# 07_DDR3.net
KiCad netlist of a schematic drawn in Altium Designer
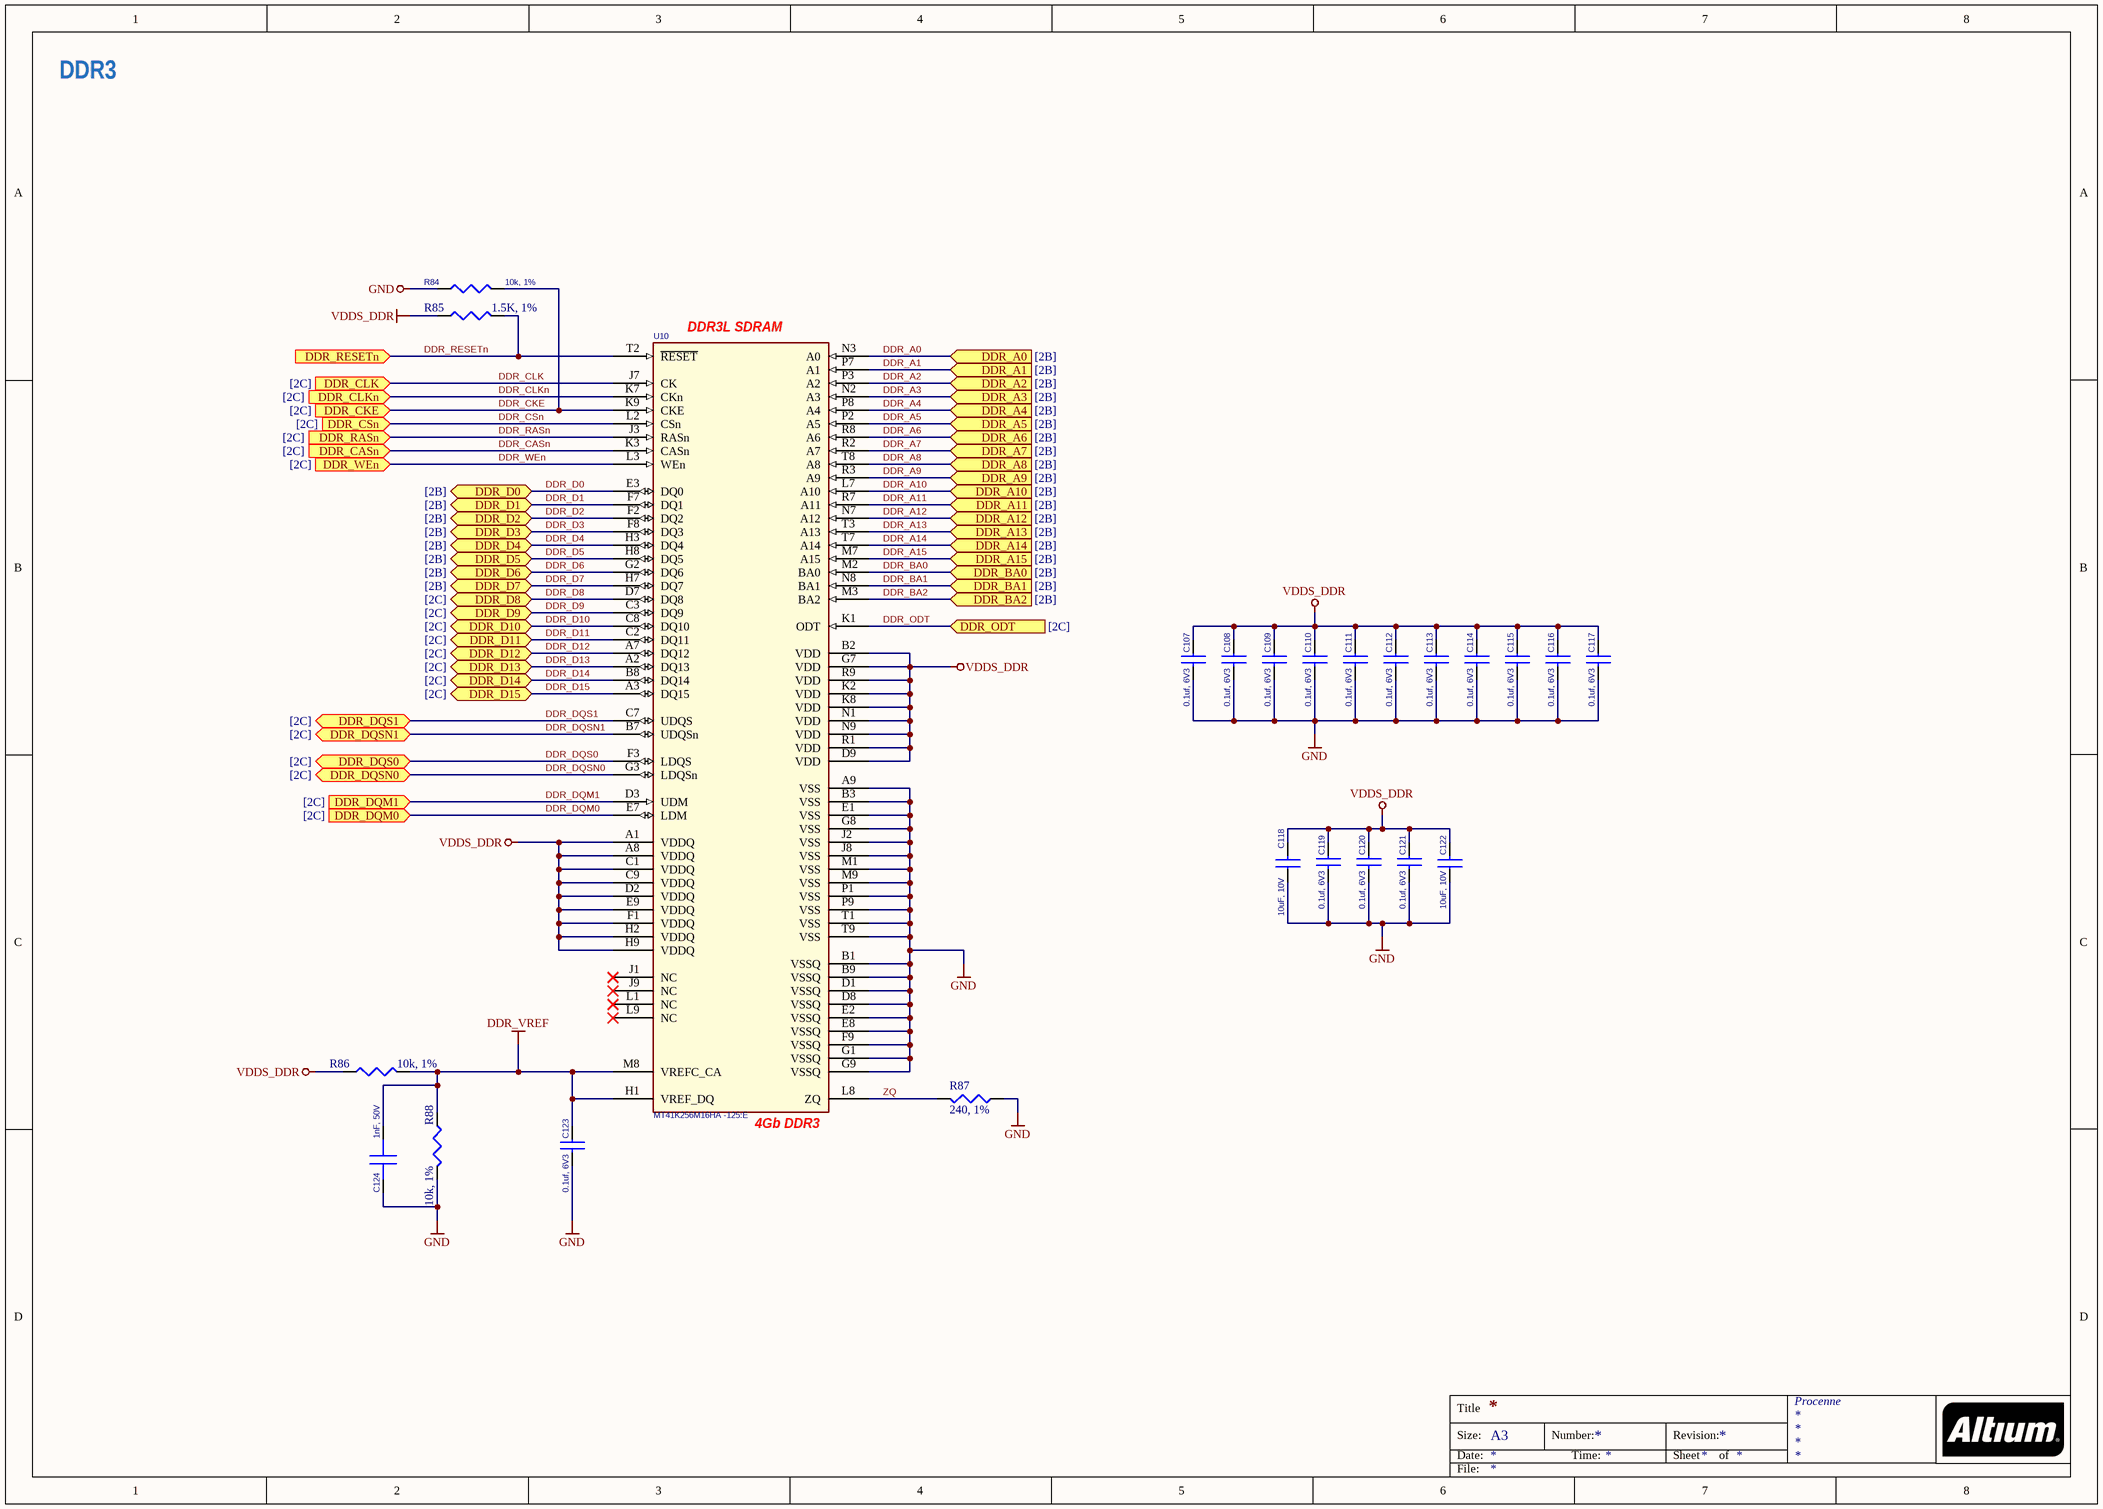
[diagram p0: 07_DDR3.SchDoc]

(export (version "E")
  (design (tool "Eeschema 10.0.6"))
  (components
    (comp (ref "C107")
      (value "0.1uf, 6V3")
      (footprint "402")
      (description "CAP CER 0.1UF 6.3V 10% X5R 0402")
      (fields
        (field (name "MANUFACTURER") "TDK Corporation")
        (field (name "MANUFACTURER PART NUMBER") "C1005X5R0J104K050BA")
      )
      (libsource (lib "BEAGLEBONEBLACK_REV A5B") (part "CAP_0.01uf_X7R_16V_10%_0402"))
    )
    (comp (ref "C108")
      (value "0.1uf, 6V3")
      (footprint "402")
      (description "CAP CER 0.1UF 6.3V 10% X5R 0402")
      (fields
        (field (name "MANUFACTURER") "TDK Corporation")
        (field (name "MANUFACTURER PART NUMBER") "C1005X5R0J104K050BA")
      )
      (libsource (lib "BEAGLEBONEBLACK_REV A5B") (part "CAP_0.01uf_X7R_16V_10%_0402"))
    )
    (comp (ref "C109")
      (value "0.1uf, 6V3")
      (footprint "402")
      (description "CAP CER 0.1UF 6.3V 10% X5R 0402")
      (fields
        (field (name "MANUFACTURER") "TDK Corporation")
        (field (name "MANUFACTURER PART NUMBER") "C1005X5R0J104K050BA")
      )
      (libsource (lib "BEAGLEBONEBLACK_REV A5B") (part "CAP_0.01uf_X7R_16V_10%_0402"))
    )
    (comp (ref "C110")
      (value "0.1uf, 6V3")
      (footprint "402")
      (description "CAP CER 0.1UF 6.3V 10% X5R 0402")
      (fields
        (field (name "MANUFACTURER") "TDK Corporation")
        (field (name "MANUFACTURER PART NUMBER") "C1005X5R0J104K050BA")
      )
      (libsource (lib "BEAGLEBONEBLACK_REV A5B") (part "CAP_0.01uf_X7R_16V_10%_0402"))
    )
    (comp (ref "C111")
      (value "0.1uf, 6V3")
      (footprint "402")
      (description "CAP CER 0.1UF 6.3V 10% X5R 0402")
      (fields
        (field (name "MANUFACTURER") "TDK Corporation")
        (field (name "MANUFACTURER PART NUMBER") "C1005X5R0J104K050BA")
      )
      (libsource (lib "BEAGLEBONEBLACK_REV A5B") (part "CAP_0.01uf_X7R_16V_10%_0402"))
    )
    (comp (ref "C112")
      (value "0.1uf, 6V3")
      (footprint "402")
      (description "CAP CER 0.1UF 6.3V 10% X5R 0402")
      (fields
        (field (name "MANUFACTURER") "TDK Corporation")
        (field (name "MANUFACTURER PART NUMBER") "C1005X5R0J104K050BA")
      )
      (libsource (lib "BEAGLEBONEBLACK_REV A5B") (part "CAP_0.01uf_X7R_16V_10%_0402"))
    )
    (comp (ref "C113")
      (value "0.1uf, 6V3")
      (footprint "402")
      (description "CAP CER 0.1UF 6.3V 10% X5R 0402")
      (fields
        (field (name "MANUFACTURER") "TDK Corporation")
        (field (name "MANUFACTURER PART NUMBER") "C1005X5R0J104K050BA")
      )
      (libsource (lib "BEAGLEBONEBLACK_REV A5B") (part "CAP_0.01uf_X7R_16V_10%_0402"))
    )
    (comp (ref "C114")
      (value "0.1uf, 6V3")
      (footprint "402")
      (description "CAP CER 0.1UF 6.3V 10% X5R 0402")
      (fields
        (field (name "MANUFACTURER") "TDK Corporation")
        (field (name "MANUFACTURER PART NUMBER") "C1005X5R0J104K050BA")
      )
      (libsource (lib "BEAGLEBONEBLACK_REV A5B") (part "CAP_0.01uf_X7R_16V_10%_0402"))
    )
    (comp (ref "C115")
      (value "0.1uf, 6V3")
      (footprint "402")
      (description "CAP CER 0.1UF 6.3V 10% X5R 0402")
      (fields
        (field (name "MANUFACTURER") "TDK Corporation")
        (field (name "MANUFACTURER PART NUMBER") "C1005X5R0J104K050BA")
      )
      (libsource (lib "BEAGLEBONEBLACK_REV A5B") (part "CAP_0.01uf_X7R_16V_10%_0402"))
    )
    (comp (ref "C116")
      (value "0.1uf, 6V3")
      (footprint "402")
      (description "CAP CER 0.1UF 6.3V 10% X5R 0402")
      (fields
        (field (name "MANUFACTURER") "TDK Corporation")
        (field (name "MANUFACTURER PART NUMBER") "C1005X5R0J104K050BA")
      )
      (libsource (lib "BEAGLEBONEBLACK_REV A5B") (part "CAP_0.01uf_X7R_16V_10%_0402"))
    )
    (comp (ref "C117")
      (value "0.1uf, 6V3")
      (footprint "402")
      (description "CAP CER 0.1UF 6.3V 10% X5R 0402")
      (fields
        (field (name "MANUFACTURER") "TDK Corporation")
        (field (name "MANUFACTURER PART NUMBER") "C1005X5R0J104K050BA")
      )
      (libsource (lib "BEAGLEBONEBLACK_REV A5B") (part "CAP_0.01uf_X7R_16V_10%_0402"))
    )
    (comp (ref "C118")
      (value "10uF, 10V")
      (footprint "805")
      (description "CAP CER 10UF 10V Y5V 0805")
      (fields
        (field (name "MANUFACTURER") "TDK Corporation")
        (field (name "MANUFACTURER PART NUMBER") "C2012Y5V1A106Z")
      )
      (libsource (lib "BEAGLEBONEBLACK_REV A5B") (part "CAP_4.7uF_X5R_6.3V_10%_0603"))
    )
    (comp (ref "C119")
      (value "0.1uf, 6V3")
      (footprint "402")
      (description "CAP CER 0.1UF 6.3V 10% X5R 0402")
      (fields
        (field (name "MANUFACTURER") "TDK Corporation")
        (field (name "MANUFACTURER PART NUMBER") "C1005X5R0J104K050BA")
      )
      (libsource (lib "BEAGLEBONEBLACK_REV A5B") (part "CAP_0.01uf_X7R_16V_10%_0402"))
    )
    (comp (ref "C120")
      (value "0.1uf, 6V3")
      (footprint "402")
      (description "CAP CER 0.1UF 6.3V 10% X5R 0402")
      (fields
        (field (name "MANUFACTURER") "TDK Corporation")
        (field (name "MANUFACTURER PART NUMBER") "C1005X5R0J104K050BA")
      )
      (libsource (lib "BEAGLEBONEBLACK_REV A5B") (part "CAP_0.01uf_X7R_16V_10%_0402"))
    )
    (comp (ref "C121")
      (value "0.1uf, 6V3")
      (footprint "402")
      (description "CAP CER 0.1UF 6.3V 10% X5R 0402")
      (fields
        (field (name "MANUFACTURER") "TDK Corporation")
        (field (name "MANUFACTURER PART NUMBER") "C1005X5R0J104K050BA")
      )
      (libsource (lib "BEAGLEBONEBLACK_REV A5B") (part "CAP_0.01uf_X7R_16V_10%_0402"))
    )
    (comp (ref "C122")
      (value "10uF, 10V")
      (footprint "805")
      (description "CAP CER 10UF 10V Y5V 0805")
      (fields
        (field (name "MANUFACTURER") "TDK Corporation")
        (field (name "MANUFACTURER PART NUMBER") "C2012Y5V1A106Z")
      )
      (libsource (lib "BEAGLEBONEBLACK_REV A5B") (part "CAP_4.7uF_X5R_6.3V_10%_0603"))
    )
    (comp (ref "C123")
      (value "0.1uf, 6V3")
      (footprint "402")
      (description "CAP CER 0.1UF 6.3V 10% X5R 0402")
      (fields
        (field (name "MANUFACTURER") "TDK Corporation")
        (field (name "MANUFACTURER PART NUMBER") "C1005X5R0J104K050BA")
      )
      (libsource (lib "BEAGLEBONEBLACK_REV A5B") (part "CAP_0.01uf_X7R_16V_10%_0402"))
    )
    (comp (ref "C124")
      (value "1nF, 50V")
      (footprint "402")
      (description "CAP CER 1000PF 16V 10% X7R 0402")
      (fields
        (field (name "MANUFACTURER") "Yageo")
        (field (name "MANUFACTURER PART NUMBER") "CC0402KRX7R7BB102")
      )
      (libsource (lib "BEAGLEBONEBLACK_REV A5B") (part "CAP SMD"))
    )
    (comp (ref "R84")
      (value "10k, 1%")
      (footprint "402")
      (description "RES 10K OHM 1/16W 5% 0402 SMD")
      (fields
        (field (name "MANUFACTURER") "Rohm Semiconductor")
        (field (name "MANUFACTURER PART NUMBER") "MCR01MZPJ103")
      )
      (libsource (lib "BEAGLEBONEBLACK_REV A5B") (part "RES_10K_1/16W_1%_0402"))
    )
    (comp (ref "R85")
      (value "1.5K, 1%")
      (footprint "402")
      (description "RES 1.50K OHM 1/16W 1% 0402 SMD")
      (fields
        (field (name "MANUFACTURER") "Yageo")
        (field (name "MANUFACTURER PART NUMBER") "RC0402FR-071K5L")
      )
      (libsource (lib "BEAGLEBONEBLACK_REV A5B") (part "RES_10K_1/16W_1%_0402"))
    )
    (comp (ref "R86")
      (value "10k, 1%")
      (footprint "402")
      (description "RES 10K OHM 1/16W 5% 0402 SMD")
      (fields
        (field (name "MANUFACTURER") "Rohm Semiconductor")
        (field (name "MANUFACTURER PART NUMBER") "MCR01MZPJ103")
      )
      (libsource (lib "BEAGLEBONEBLACK_REV A5B") (part "RES_10K_1/16W_1%_0402"))
    )
    (comp (ref "R87")
      (value "240, 1%")
      (footprint "402")
      (description "RES 240 OHM 1/10W 5% 0402 SMD")
      (fields
        (field (name "MANUFACTURER") "Yageo")
        (field (name "MANUFACTURER PART NUMBER") "RC0402FR-07240RL")
      )
      (libsource (lib "BEAGLEBONEBLACK_REV A5B") (part "RES_10K_1/16W_1%_0402"))
    )
    (comp (ref "R88")
      (value "10k, 1%")
      (footprint "402")
      (description "RES 10K OHM 1/16W 5% 0402 SMD")
      (fields
        (field (name "MANUFACTURER") "Rohm Semiconductor")
        (field (name "MANUFACTURER PART NUMBER") "MCR01MZPJ103")
      )
      (libsource (lib "BEAGLEBONEBLACK_REV A5B") (part "RES_10K_1/16W_1%_0402"))
    )
    (comp (ref "U10")
      (value "MT41K256M16HA -125:E")
      (footprint "BGA96_T9_P8_9X14")
      (description "DDR2 SDRAM 2Gb (256Mx8)")
      (fields
        (field (name "MANUFACTURER") "Micron Technology")
        (field (name "MANUFACTURER PART NUMBER") "MT41K256M16HA-125:E")
      )
      (libsource (lib "BEAGLEBONEBLACK_REV A5B") (part "MT41K256M16HA"))
    )
  )
  (nets
    (net (code "1") (name "/DDR_A0") (class "Default")
      (node (ref "U10") (pin "N3") (pinfunction "A0_N3") (pintype "input"))
    )
    (net (code "2") (name "/DDR_A1") (class "Default")
      (node (ref "U10") (pin "P7") (pinfunction "A1_P7") (pintype "input"))
    )
    (net (code "3") (name "/DDR_A2") (class "Default")
      (node (ref "U10") (pin "P3") (pinfunction "A2_P3") (pintype "input"))
    )
    (net (code "4") (name "/DDR_A3") (class "Default")
      (node (ref "U10") (pin "N2") (pinfunction "A3_N2") (pintype "input"))
    )
    (net (code "5") (name "/DDR_A4") (class "Default")
      (node (ref "U10") (pin "P8") (pinfunction "A4_P8") (pintype "input"))
    )
    (net (code "6") (name "/DDR_A5") (class "Default")
      (node (ref "U10") (pin "P2") (pinfunction "A5_P2") (pintype "input"))
    )
    (net (code "7") (name "/DDR_A6") (class "Default")
      (node (ref "U10") (pin "R8") (pinfunction "A6_R8") (pintype "input"))
    )
    (net (code "8") (name "/DDR_A7") (class "Default")
      (node (ref "U10") (pin "R2") (pinfunction "A7_R2") (pintype "input"))
    )
    (net (code "9") (name "/DDR_A8") (class "Default")
      (node (ref "U10") (pin "T8") (pinfunction "A8_T8") (pintype "input"))
    )
    (net (code "10") (name "/DDR_A9") (class "Default")
      (node (ref "U10") (pin "R3") (pinfunction "A9_R3") (pintype "input"))
    )
    (net (code "11") (name "/DDR_A10") (class "Default")
      (node (ref "U10") (pin "L7") (pinfunction "A10_L7") (pintype "input"))
    )
    (net (code "12") (name "/DDR_A11") (class "Default")
      (node (ref "U10") (pin "R7") (pinfunction "A11_R7") (pintype "input"))
    )
    (net (code "13") (name "/DDR_A12") (class "Default")
      (node (ref "U10") (pin "N7") (pinfunction "A12_N7") (pintype "input"))
    )
    (net (code "14") (name "/DDR_A13") (class "Default")
      (node (ref "U10") (pin "T3") (pinfunction "A13_T3") (pintype "input"))
    )
    (net (code "15") (name "/DDR_A14") (class "Default")
      (node (ref "U10") (pin "T7") (pinfunction "A14_T7") (pintype "input"))
    )
    (net (code "16") (name "/DDR_A15") (class "Default")
      (node (ref "U10") (pin "M7") (pinfunction "A15_M7") (pintype "input"))
    )
    (net (code "17") (name "/DDR_BA0") (class "Default")
      (node (ref "U10") (pin "M2") (pinfunction "BA0_M2") (pintype "input"))
    )
    (net (code "18") (name "/DDR_BA1") (class "Default")
      (node (ref "U10") (pin "N8") (pinfunction "BA1_N8") (pintype "input"))
    )
    (net (code "19") (name "/DDR_BA2") (class "Default")
      (node (ref "U10") (pin "M3") (pinfunction "BA2_M3") (pintype "input"))
    )
    (net (code "20") (name "/DDR_CASn") (class "Default")
      (node (ref "U10") (pin "K3") (pinfunction "CASn_K3") (pintype "input"))
    )
    (net (code "21") (name "/DDR_CKE") (class "Default")
      (node (ref "R84") (pin "2") (pinfunction "2_2") (pintype "passive"))
      (node (ref "U10") (pin "K9") (pinfunction "CKE_K9") (pintype "input"))
    )
    (net (code "22") (name "/DDR_CLK") (class "Default")
      (node (ref "U10") (pin "J7") (pinfunction "CK_J7") (pintype "input"))
    )
    (net (code "23") (name "/DDR_CLKn") (class "Default")
      (node (ref "U10") (pin "K7") (pinfunction "CKn_K7") (pintype "input"))
    )
    (net (code "24") (name "/DDR_CSn") (class "Default")
      (node (ref "U10") (pin "L2") (pinfunction "CSn_L2") (pintype "input"))
    )
    (net (code "25") (name "/DDR_D0") (class "Default")
      (node (ref "U10") (pin "E3") (pinfunction "DQ0_E3") (pintype "bidirectional"))
    )
    (net (code "26") (name "/DDR_D1") (class "Default")
      (node (ref "U10") (pin "F7") (pinfunction "DQ1_F7") (pintype "bidirectional"))
    )
    (net (code "27") (name "/DDR_D2") (class "Default")
      (node (ref "U10") (pin "F2") (pinfunction "DQ2_F2") (pintype "bidirectional"))
    )
    (net (code "28") (name "/DDR_D3") (class "Default")
      (node (ref "U10") (pin "F8") (pinfunction "DQ3_F8") (pintype "bidirectional"))
    )
    (net (code "29") (name "/DDR_D4") (class "Default")
      (node (ref "U10") (pin "H3") (pinfunction "DQ4_H3") (pintype "bidirectional"))
    )
    (net (code "30") (name "/DDR_D5") (class "Default")
      (node (ref "U10") (pin "H8") (pinfunction "DQ5_H8") (pintype "bidirectional"))
    )
    (net (code "31") (name "/DDR_D6") (class "Default")
      (node (ref "U10") (pin "G2") (pinfunction "DQ6_G2") (pintype "bidirectional"))
    )
    (net (code "32") (name "/DDR_D7") (class "Default")
      (node (ref "U10") (pin "H7") (pinfunction "DQ7_H7") (pintype "bidirectional"))
    )
    (net (code "33") (name "/DDR_D8") (class "Default")
      (node (ref "U10") (pin "D7") (pinfunction "DQ8_D7") (pintype "bidirectional"))
    )
    (net (code "34") (name "/DDR_D9") (class "Default")
      (node (ref "U10") (pin "C3") (pinfunction "DQ9_C3") (pintype "bidirectional"))
    )
    (net (code "35") (name "/DDR_D10") (class "Default")
      (node (ref "U10") (pin "C8") (pinfunction "DQ10_C8") (pintype "bidirectional"))
    )
    (net (code "36") (name "/DDR_D11") (class "Default")
      (node (ref "U10") (pin "C2") (pinfunction "DQ11_C2") (pintype "bidirectional"))
    )
    (net (code "37") (name "/DDR_D12") (class "Default")
      (node (ref "U10") (pin "A7") (pinfunction "DQ12_A7") (pintype "bidirectional"))
    )
    (net (code "38") (name "/DDR_D13") (class "Default")
      (node (ref "U10") (pin "A2") (pinfunction "DQ13_A2") (pintype "bidirectional"))
    )
    (net (code "39") (name "/DDR_D14") (class "Default")
      (node (ref "U10") (pin "B8") (pinfunction "DQ14_B8") (pintype "bidirectional"))
    )
    (net (code "40") (name "/DDR_D15") (class "Default")
      (node (ref "U10") (pin "A3") (pinfunction "DQ15_A3") (pintype "bidirectional"))
    )
    (net (code "41") (name "/DDR_DQM0") (class "Default")
      (node (ref "U10") (pin "E7") (pinfunction "LDM_E7") (pintype "bidirectional"))
    )
    (net (code "42") (name "/DDR_DQM1") (class "Default")
      (node (ref "U10") (pin "D3") (pinfunction "UDM_D3") (pintype "input"))
    )
    (net (code "43") (name "/DDR_DQS0") (class "Default")
      (node (ref "U10") (pin "F3") (pinfunction "LDQS_F3") (pintype "bidirectional"))
    )
    (net (code "44") (name "/DDR_DQS1") (class "Default")
      (node (ref "U10") (pin "C7") (pinfunction "UDQS_C7") (pintype "bidirectional"))
    )
    (net (code "45") (name "/DDR_DQSN0") (class "Default")
      (node (ref "U10") (pin "G3") (pinfunction "LDQSn_G3") (pintype "bidirectional"))
    )
    (net (code "46") (name "/DDR_DQSN1") (class "Default")
      (node (ref "U10") (pin "B7") (pinfunction "UDQSn_B7") (pintype "bidirectional"))
    )
    (net (code "47") (name "/DDR_ODT") (class "Default")
      (node (ref "U10") (pin "K1") (pinfunction "ODT_K1") (pintype "input"))
    )
    (net (code "48") (name "/DDR_RASn") (class "Default")
      (node (ref "U10") (pin "J3") (pinfunction "RASn_J3") (pintype "input"))
    )
    (net (code "49") (name "/DDR_RESETn") (class "Default")
      (node (ref "R85") (pin "2") (pinfunction "2_2") (pintype "passive"))
      (node (ref "U10") (pin "T2") (pinfunction "~{RESET}_T2") (pintype "input"))
    )
    (net (code "50") (name "/DDR_WEn") (class "Default")
      (node (ref "U10") (pin "L3") (pinfunction "WEn_L3") (pintype "input"))
    )
    (net (code "51") (name "/ZQ") (class "Default")
      (node (ref "R87") (pin "2") (pinfunction "2_2") (pintype "passive"))
      (node (ref "U10") (pin "L8") (pinfunction "ZQ_L8") (pintype "passive"))
    )
    (net (code "52") (name "DDR_VREF") (class "Default")
      (node (ref "C123") (pin "1") (pinfunction "1_1") (pintype "passive"))
      (node (ref "C124") (pin "1") (pinfunction "1_1") (pintype "passive"))
      (node (ref "R86") (pin "2") (pinfunction "2_2") (pintype "passive"))
      (node (ref "R88") (pin "1") (pinfunction "1_1") (pintype "passive"))
      (node (ref "U10") (pin "H1") (pinfunction "VREF_DQ_H1") (pintype "passive"))
      (node (ref "U10") (pin "M8") (pinfunction "VREFC_CA_M8") (pintype "power_in"))
    )
    (net (code "53") (name "GND") (class "Default")
      (node (ref "C107") (pin "2") (pinfunction "2_2") (pintype "passive"))
      (node (ref "C108") (pin "2") (pinfunction "2_2") (pintype "passive"))
      (node (ref "C109") (pin "2") (pinfunction "2_2") (pintype "passive"))
      (node (ref "C110") (pin "2") (pinfunction "2_2") (pintype "passive"))
      (node (ref "C111") (pin "2") (pinfunction "2_2") (pintype "passive"))
      (node (ref "C112") (pin "2") (pinfunction "2_2") (pintype "passive"))
      (node (ref "C113") (pin "2") (pinfunction "2_2") (pintype "passive"))
      (node (ref "C114") (pin "2") (pinfunction "2_2") (pintype "passive"))
      (node (ref "C115") (pin "2") (pinfunction "2_2") (pintype "passive"))
      (node (ref "C116") (pin "2") (pinfunction "2_2") (pintype "passive"))
      (node (ref "C117") (pin "2") (pinfunction "2_2") (pintype "passive"))
      (node (ref "C118") (pin "1") (pinfunction "1_1") (pintype "passive"))
      (node (ref "C119") (pin "2") (pinfunction "2_2") (pintype "passive"))
      (node (ref "C120") (pin "2") (pinfunction "2_2") (pintype "passive"))
      (node (ref "C121") (pin "2") (pinfunction "2_2") (pintype "passive"))
      (node (ref "C122") (pin "1") (pinfunction "1_1") (pintype "passive"))
      (node (ref "C123") (pin "2") (pinfunction "2_2") (pintype "passive"))
      (node (ref "C124") (pin "2") (pinfunction "2_2") (pintype "passive"))
      (node (ref "R84") (pin "1") (pinfunction "1_1") (pintype "passive"))
      (node (ref "R87") (pin "1") (pinfunction "1_1") (pintype "passive"))
      (node (ref "R88") (pin "2") (pinfunction "2_2") (pintype "passive"))
      (node (ref "U10") (pin "A9") (pinfunction "VSS_A9") (pintype "power_in"))
      (node (ref "U10") (pin "B1") (pinfunction "VSSQ_B1") (pintype "power_in"))
      (node (ref "U10") (pin "B3") (pinfunction "VSS_B3") (pintype "power_in"))
      (node (ref "U10") (pin "B9") (pinfunction "VSSQ_B9") (pintype "power_in"))
      (node (ref "U10") (pin "D1") (pinfunction "VSSQ_D1") (pintype "power_in"))
      (node (ref "U10") (pin "D8") (pinfunction "VSSQ_D8") (pintype "power_in"))
      (node (ref "U10") (pin "E1") (pinfunction "VSS_E1") (pintype "power_in"))
      (node (ref "U10") (pin "E2") (pinfunction "VSSQ_E2") (pintype "power_in"))
      (node (ref "U10") (pin "E8") (pinfunction "VSSQ_E8") (pintype "power_in"))
      (node (ref "U10") (pin "F9") (pinfunction "VSSQ_F9") (pintype "power_in"))
      (node (ref "U10") (pin "G1") (pinfunction "VSSQ_G1") (pintype "power_in"))
      (node (ref "U10") (pin "G8") (pinfunction "VSS_G8") (pintype "power_in"))
      (node (ref "U10") (pin "G9") (pinfunction "VSSQ_G9") (pintype "power_in"))
      (node (ref "U10") (pin "J2") (pinfunction "VSS_J2") (pintype "power_in"))
      (node (ref "U10") (pin "J8") (pinfunction "VSS_J8") (pintype "power_in"))
      (node (ref "U10") (pin "M1") (pinfunction "VSS_M1") (pintype "power_in"))
      (node (ref "U10") (pin "M9") (pinfunction "VSS_M9") (pintype "power_in"))
      (node (ref "U10") (pin "P1") (pinfunction "VSS_P1") (pintype "power_in"))
      (node (ref "U10") (pin "P9") (pinfunction "VSS_P9") (pintype "power_in"))
      (node (ref "U10") (pin "T1") (pinfunction "VSS_T1") (pintype "power_in"))
      (node (ref "U10") (pin "T9") (pinfunction "VSS_T9") (pintype "power_in"))
    )
    (net (code "54") (name "VDDS_DDR") (class "Default")
      (node (ref "C107") (pin "1") (pinfunction "1_1") (pintype "passive"))
      (node (ref "C108") (pin "1") (pinfunction "1_1") (pintype "passive"))
      (node (ref "C109") (pin "1") (pinfunction "1_1") (pintype "passive"))
      (node (ref "C110") (pin "1") (pinfunction "1_1") (pintype "passive"))
      (node (ref "C111") (pin "1") (pinfunction "1_1") (pintype "passive"))
      (node (ref "C112") (pin "1") (pinfunction "1_1") (pintype "passive"))
      (node (ref "C113") (pin "1") (pinfunction "1_1") (pintype "passive"))
      (node (ref "C114") (pin "1") (pinfunction "1_1") (pintype "passive"))
      (node (ref "C115") (pin "1") (pinfunction "1_1") (pintype "passive"))
      (node (ref "C116") (pin "1") (pinfunction "1_1") (pintype "passive"))
      (node (ref "C117") (pin "1") (pinfunction "1_1") (pintype "passive"))
      (node (ref "C118") (pin "2") (pinfunction "2_2") (pintype "passive"))
      (node (ref "C119") (pin "1") (pinfunction "1_1") (pintype "passive"))
      (node (ref "C120") (pin "1") (pinfunction "1_1") (pintype "passive"))
      (node (ref "C121") (pin "1") (pinfunction "1_1") (pintype "passive"))
      (node (ref "C122") (pin "2") (pinfunction "2_2") (pintype "passive"))
      (node (ref "R85") (pin "1") (pinfunction "1_1") (pintype "passive"))
      (node (ref "R86") (pin "1") (pinfunction "1_1") (pintype "passive"))
      (node (ref "U10") (pin "A1") (pinfunction "VDDQ_A1") (pintype "power_in"))
      (node (ref "U10") (pin "A8") (pinfunction "VDDQ_A8") (pintype "power_in"))
      (node (ref "U10") (pin "B2") (pinfunction "VDD_B2") (pintype "power_in"))
      (node (ref "U10") (pin "C1") (pinfunction "VDDQ_C1") (pintype "power_in"))
      (node (ref "U10") (pin "C9") (pinfunction "VDDQ_C9") (pintype "power_in"))
      (node (ref "U10") (pin "D2") (pinfunction "VDDQ_D2") (pintype "power_in"))
      (node (ref "U10") (pin "D9") (pinfunction "VDD_D9") (pintype "power_in"))
      (node (ref "U10") (pin "E9") (pinfunction "VDDQ_E9") (pintype "power_in"))
      (node (ref "U10") (pin "F1") (pinfunction "VDDQ_F1") (pintype "power_in"))
      (node (ref "U10") (pin "G7") (pinfunction "VDD_G7") (pintype "power_in"))
      (node (ref "U10") (pin "H2") (pinfunction "VDDQ_H2") (pintype "power_in"))
      (node (ref "U10") (pin "H9") (pinfunction "VDDQ_H9") (pintype "power_in"))
      (node (ref "U10") (pin "K2") (pinfunction "VDD_K2") (pintype "power_in"))
      (node (ref "U10") (pin "K8") (pinfunction "VDD_K8") (pintype "power_in"))
      (node (ref "U10") (pin "N1") (pinfunction "VDD_N1") (pintype "power_in"))
      (node (ref "U10") (pin "N9") (pinfunction "VDD_N9") (pintype "power_in"))
      (node (ref "U10") (pin "R1") (pinfunction "VDD_R1") (pintype "power_in"))
      (node (ref "U10") (pin "R9") (pinfunction "VDD_R9") (pintype "power_in"))
    )
    (net (code "55") (name "unconnected-(U10-NC-PadJ1)") (class "Default")
      (node (ref "U10") (pin "J1") (pinfunction "NC_J1") (pintype "passive+no_connect"))
    )
    (net (code "56") (name "unconnected-(U10-NC-PadJ9)") (class "Default")
      (node (ref "U10") (pin "J9") (pinfunction "NC_J9") (pintype "passive+no_connect"))
    )
    (net (code "57") (name "unconnected-(U10-NC-PadL1)") (class "Default")
      (node (ref "U10") (pin "L1") (pinfunction "NC_L1") (pintype "power_in+no_connect"))
    )
    (net (code "58") (name "unconnected-(U10-NC-PadL9)") (class "Default")
      (node (ref "U10") (pin "L9") (pinfunction "NC_L9") (pintype "power_in+no_connect"))
    )
  )
)
